# pir_schematic.net
KiCad netlist of a schematic drawn in Altium Designer
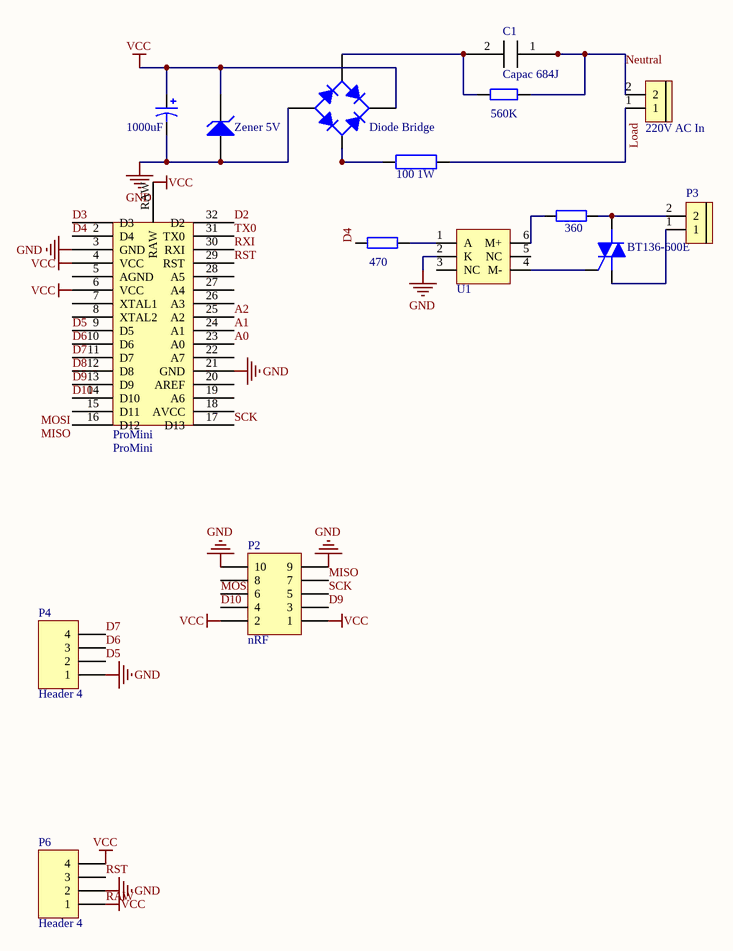
[diagram p0: pir_schematic.SchDoc]

(export (version "E")
  (design (tool "Eeschema 10.0.6"))
  (components
    (comp (ref "C1")
      (value "Capac 684J")
      (footprint "Tu keo 684J 400V")
      (libsource (lib "ArduinoLib") (part "Tu keo 684J 400V"))
    )
    (comp (ref "C3")
      (value "1000uF")
      (footprint "C10mm")
      (description "Polarized Capacitor (Axial)")
      (fields (field (name "PUBLISHER") "Altium Limited"))
      (libsource (lib "NBBLib 14-03-2012") (part "Cap Pol 8mm"))
    )
    (comp (ref "D1")
      (value "Diode Bridge")
      (footprint "D-38")
      (description "Full Wave Diode Bridge")
      (fields (field (name "PUBLISHER") "Altium Limited"))
      (libsource (lib "Miscellaneous Devices") (part "Bridge1"))
    )
    (comp (ref "D3")
      (value "Zener 5V")
      (footprint "DIODE/NOM/0.5A")
      (description "Zener Diode")
      (fields (field (name "VOLTAGE") "5") (field (name "PUBLISHER") "Altium Limited"))
      (libsource (lib "NBBLib 14-03-2012") (part "Diode Zener"))
    )
    (comp (ref "P1")
      (value "220V AC In")
      (footprint "BIG_Header 2")
      (libsource (lib "NBBLib 14-03-2012") (part "BIG_Header 2"))
    )
    (comp (ref "P2")
      (value "nRF")
      (footprint "HDR2X5")
      (description "Header, 5-Pin, Dual row")
      (fields (field (name "PUBLISHER") "Altium Limited"))
      (libsource (lib "Miscellaneous Connectors") (part "Header 5X2"))
    )
    (comp (ref "P3")
      (value "BIG_Header 2")
      (footprint "BIG_Header 2")
      (libsource (lib "NBBLib 14-03-2012") (part "BIG_Header 2"))
    )
    (comp (ref "P4")
      (value "Header 4")
      (footprint "HDR1X4")
      (description "Header, 4-Pin")
      (fields (field (name "PUBLISHER") "Altium Limited"))
      (libsource (lib "Miscellaneous Connectors") (part "Header 4"))
    )
    (comp (ref "P6")
      (value "Header 4")
      (footprint "HDR1X4")
      (description "Header, 4-Pin")
      (fields (field (name "PUBLISHER") "Altium Limited"))
      (libsource (lib "Miscellaneous Connectors") (part "Header 4"))
    )
    (comp (ref "ProMini")
      (value "ProMini")
      (footprint "Arduino Pro Mini")
      (libsource (lib "ArduinoLib") (part "Pro Mini"))
    )
    (comp (ref "Q1")
      (value "BT136-600E")
      (footprint "BTA6-600")
      (description "Silicon Bidirectional Triode Thyristor")
      (fields (field (name "PUBLISHER") "Altium Limited"))
      (libsource (lib "NBBLib 14-03-2012") (part "BTA12-600"))
    )
    (comp (ref "R1")
      (value "100 1W")
      (footprint "DIEN TRO 1W (tube)")
      (description "1W Res Power")
      (fields (field (name "VOLTAGE") "400") (field (name "CREATOR") "Nguyen Ba Bien"))
      (libsource (lib "NBBLib 14-03-2012") (part "Res 1W"))
    )
    (comp (ref "R3")
      (value "560K")
      (footprint "AXIAL-0.4")
      (description "Resistor")
      (fields (field (name "PUBLISHER") "Altium Limited"))
      (libsource (lib "Miscellaneous Devices") (part "Res2"))
    )
    (comp (ref "R4")
      (value "470")
      (footprint "R1/4W")
      (description "Resistor")
      (libsource (lib "t.thien") (part "R1/4W"))
    )
    (comp (ref "R5")
      (value "360")
      (footprint "R1/4W")
      (description "Resistor")
      (libsource (lib "t.thien") (part "R1/4W"))
    )
    (comp (ref "U1")
      (value "MOC3021M")
      (footprint "MOC30XX")
      (libsource (lib "NBBLib 14-03-2012") (part "MOC3021M"))
    )
  )
  (nets
    (net (code "1") (name "/A0") (class "Default")
      (node (ref "ProMini") (pin "23") (pinfunction "A0_23") (pintype "passive"))
    )
    (net (code "2") (name "/A1") (class "Default")
      (node (ref "ProMini") (pin "24") (pinfunction "A1_24") (pintype "passive"))
    )
    (net (code "3") (name "/A2") (class "Default")
      (node (ref "ProMini") (pin "25") (pinfunction "A2_25") (pintype "passive"))
    )
    (net (code "4") (name "/D2") (class "Default")
      (node (ref "ProMini") (pin "32") (pinfunction "D2_32") (pintype "passive"))
    )
    (net (code "5") (name "/D3") (class "Default")
      (node (ref "ProMini") (pin "1") (pinfunction "D3_1") (pintype "passive"))
    )
    (net (code "6") (name "/D4") (class "Default")
      (node (ref "ProMini") (pin "2") (pinfunction "D4_2") (pintype "passive"))
      (node (ref "R4") (pin "1") (pinfunction "1_1") (pintype "passive"))
    )
    (net (code "7") (name "/D5") (class "Default")
      (node (ref "P4") (pin "2") (pinfunction "2_2") (pintype "passive"))
      (node (ref "ProMini") (pin "9") (pinfunction "D5_9") (pintype "passive"))
    )
    (net (code "8") (name "/D6") (class "Default")
      (node (ref "P4") (pin "3") (pinfunction "3_3") (pintype "passive"))
      (node (ref "ProMini") (pin "10") (pinfunction "D6_10") (pintype "passive"))
    )
    (net (code "9") (name "/D7") (class "Default")
      (node (ref "P4") (pin "4") (pinfunction "4_4") (pintype "passive"))
      (node (ref "ProMini") (pin "11") (pinfunction "D7_11") (pintype "passive"))
    )
    (net (code "10") (name "/D8") (class "Default")
      (node (ref "ProMini") (pin "12") (pinfunction "D8_12") (pintype "passive"))
    )
    (net (code "11") (name "/D9") (class "Default")
      (node (ref "P2") (pin "3") (pinfunction "3_3") (pintype "passive"))
      (node (ref "ProMini") (pin "13") (pinfunction "D9_13") (pintype "passive"))
    )
    (net (code "12") (name "/D10") (class "Default")
      (node (ref "P2") (pin "4") (pinfunction "4_4") (pintype "passive"))
      (node (ref "ProMini") (pin "14") (pinfunction "D10_14") (pintype "passive"))
    )
    (net (code "13") (name "/Load") (class "Default")
      (node (ref "P1") (pin "1") (pinfunction "1_1") (pintype "passive"))
      (node (ref "R1") (pin "2") (pinfunction "2_2") (pintype "passive"))
    )
    (net (code "14") (name "/MISO") (class "Default")
      (node (ref "P2") (pin "7") (pinfunction "7_7") (pintype "passive"))
      (node (ref "ProMini") (pin "16") (pinfunction "D12_16") (pintype "passive"))
    )
    (net (code "15") (name "/MOSI") (class "Default")
      (node (ref "P2") (pin "6") (pinfunction "6_6") (pintype "passive"))
      (node (ref "ProMini") (pin "15") (pinfunction "D11_15") (pintype "passive"))
    )
    (net (code "16") (name "/Neutral") (class "Default")
      (node (ref "C1") (pin "1") (pinfunction "1_1") (pintype "passive"))
      (node (ref "P1") (pin "2") (pinfunction "2_2") (pintype "passive"))
      (node (ref "R3") (pin "2") (pinfunction "2_2") (pintype "passive"))
    )
    (net (code "17") (name "/RST") (class "Default")
      (node (ref "P6") (pin "3") (pinfunction "3_3") (pintype "passive"))
      (node (ref "ProMini") (pin "29") (pinfunction "RST_29") (pintype "passive"))
    )
    (net (code "18") (name "/RXI") (class "Default")
      (node (ref "ProMini") (pin "30") (pinfunction "RXI_30") (pintype "passive"))
    )
    (net (code "19") (name "/SCK") (class "Default")
      (node (ref "P2") (pin "5") (pinfunction "5_5") (pintype "passive"))
      (node (ref "ProMini") (pin "17") (pinfunction "D13_17") (pintype "passive"))
    )
    (net (code "20") (name "/TX0") (class "Default")
      (node (ref "ProMini") (pin "31") (pinfunction "TX0_31") (pintype "passive"))
    )
    (net (code "21") (name "GND") (class "Default")
      (node (ref "C3") (pin "2") (pinfunction "2_2") (pintype "passive"))
      (node (ref "D1") (pin "3") (pinfunction "A_3") (pintype "passive"))
      (node (ref "D3") (pin "1") (pinfunction "A_1") (pintype "passive"))
      (node (ref "P2") (pin "10") (pinfunction "10_10") (pintype "passive"))
      (node (ref "P2") (pin "9") (pinfunction "9_9") (pintype "passive"))
      (node (ref "P4") (pin "1") (pinfunction "1_1") (pintype "passive"))
      (node (ref "P6") (pin "2") (pinfunction "2_2") (pintype "passive"))
      (node (ref "ProMini") (pin "21") (pinfunction "GND_21") (pintype "passive"))
      (node (ref "ProMini") (pin "3") (pinfunction "GND_3") (pintype "passive"))
      (node (ref "U1") (pin "2") (pinfunction "K_2") (pintype "passive"))
    )
    (net (code "22") (name "Net-(C1-Pad2)") (class "Default")
      (node (ref "C1") (pin "2") (pinfunction "2_2") (pintype "passive"))
      (node (ref "D1") (pin "4") (pinfunction "C_4") (pintype "passive"))
      (node (ref "R3") (pin "1") (pinfunction "1_1") (pintype "passive"))
    )
    (net (code "23") (name "Net-(D1-C-Pad2)") (class "Default")
      (node (ref "D1") (pin "2") (pinfunction "C_2") (pintype "passive"))
      (node (ref "R1") (pin "1") (pinfunction "1_1") (pintype "passive"))
    )
    (net (code "24") (name "Net-(Q1-G)") (class "Default")
      (node (ref "Q1") (pin "3") (pinfunction "G_3") (pintype "passive"))
      (node (ref "U1") (pin "4") (pinfunction "M-_4") (pintype "passive"))
    )
    (net (code "25") (name "Net-(Q1-M1)") (class "Default")
      (node (ref "P3") (pin "1") (pinfunction "1_1") (pintype "passive"))
      (node (ref "Q1") (pin "1") (pinfunction "M1_1") (pintype "passive"))
    )
    (net (code "26") (name "Net-(Q1-M2)") (class "Default")
      (node (ref "P3") (pin "2") (pinfunction "2_2") (pintype "passive"))
      (node (ref "Q1") (pin "2") (pinfunction "M2_2") (pintype "passive"))
      (node (ref "R5") (pin "2") (pinfunction "2_2") (pintype "passive"))
    )
    (net (code "27") (name "Net-(U1-A)") (class "Default")
      (node (ref "R4") (pin "2") (pinfunction "2_2") (pintype "passive"))
      (node (ref "U1") (pin "1") (pinfunction "A_1") (pintype "passive"))
    )
    (net (code "28") (name "Net-(U1-M+)") (class "Default")
      (node (ref "R5") (pin "1") (pinfunction "1_1") (pintype "passive"))
      (node (ref "U1") (pin "6") (pinfunction "M+_6") (pintype "passive"))
    )
    (net (code "29") (name "VCC") (class "Default")
      (node (ref "C3") (pin "1") (pinfunction "1_1") (pintype "passive"))
      (node (ref "D1") (pin "1") (pinfunction "K_1") (pintype "passive"))
      (node (ref "D3") (pin "2") (pinfunction "K_2") (pintype "passive"))
      (node (ref "P2") (pin "1") (pinfunction "1_1") (pintype "passive"))
      (node (ref "P2") (pin "2") (pinfunction "2_2") (pintype "passive"))
      (node (ref "P6") (pin "1") (pinfunction "1_1") (pintype "passive"))
      (node (ref "P6") (pin "4") (pinfunction "4_4") (pintype "passive"))
      (node (ref "ProMini") (pin "4") (pinfunction "VCC_4") (pintype "passive"))
      (node (ref "ProMini") (pin "6") (pinfunction "VCC_6") (pintype "passive"))
      (node (ref "ProMini") (pin "RAW") (pinfunction "RAW_RAW") (pintype "passive"))
    )
    (net (code "30") (name "unconnected-(P2-Pad8)") (class "Default")
      (node (ref "P2") (pin "8") (pinfunction "8_8") (pintype "passive"))
    )
    (net (code "31") (name "unconnected-(ProMini-A3-Pad26)") (class "Default")
      (node (ref "ProMini") (pin "26") (pinfunction "A3_26") (pintype "passive"))
    )
    (net (code "32") (name "unconnected-(ProMini-A4-Pad27)") (class "Default")
      (node (ref "ProMini") (pin "27") (pinfunction "A4_27") (pintype "passive"))
    )
    (net (code "33") (name "unconnected-(ProMini-A5-Pad28)") (class "Default")
      (node (ref "ProMini") (pin "28") (pinfunction "A5_28") (pintype "passive"))
    )
    (net (code "34") (name "unconnected-(ProMini-A6-Pad19)") (class "Default")
      (node (ref "ProMini") (pin "19") (pinfunction "A6_19") (pintype "passive"))
    )
    (net (code "35") (name "unconnected-(ProMini-A7-Pad22)") (class "Default")
      (node (ref "ProMini") (pin "22") (pinfunction "A7_22") (pintype "passive"))
    )
    (net (code "36") (name "unconnected-(ProMini-AGND-Pad5)") (class "Default")
      (node (ref "ProMini") (pin "5") (pinfunction "AGND_5") (pintype "passive"))
    )
    (net (code "37") (name "unconnected-(ProMini-AREF-Pad20)") (class "Default")
      (node (ref "ProMini") (pin "20") (pinfunction "AREF_20") (pintype "passive"))
    )
    (net (code "38") (name "unconnected-(ProMini-AVCC-Pad18)") (class "Default")
      (node (ref "ProMini") (pin "18") (pinfunction "AVCC_18") (pintype "passive"))
    )
    (net (code "39") (name "unconnected-(ProMini-XTAL1-Pad7)") (class "Default")
      (node (ref "ProMini") (pin "7") (pinfunction "XTAL1_7") (pintype "passive"))
    )
    (net (code "40") (name "unconnected-(ProMini-XTAL2-Pad8)") (class "Default")
      (node (ref "ProMini") (pin "8") (pinfunction "XTAL2_8") (pintype "passive"))
    )
    (net (code "41") (name "unconnected-(U1-NC-Pad3)") (class "Default")
      (node (ref "U1") (pin "3") (pinfunction "NC_3") (pintype "passive"))
    )
    (net (code "42") (name "unconnected-(U1-NC-Pad5)") (class "Default")
      (node (ref "U1") (pin "5") (pinfunction "NC_5") (pintype "passive"))
    )
  )
)
